# Multi-Sensor-V2_0.net
KiCad netlist of a schematic drawn in Altium Designer
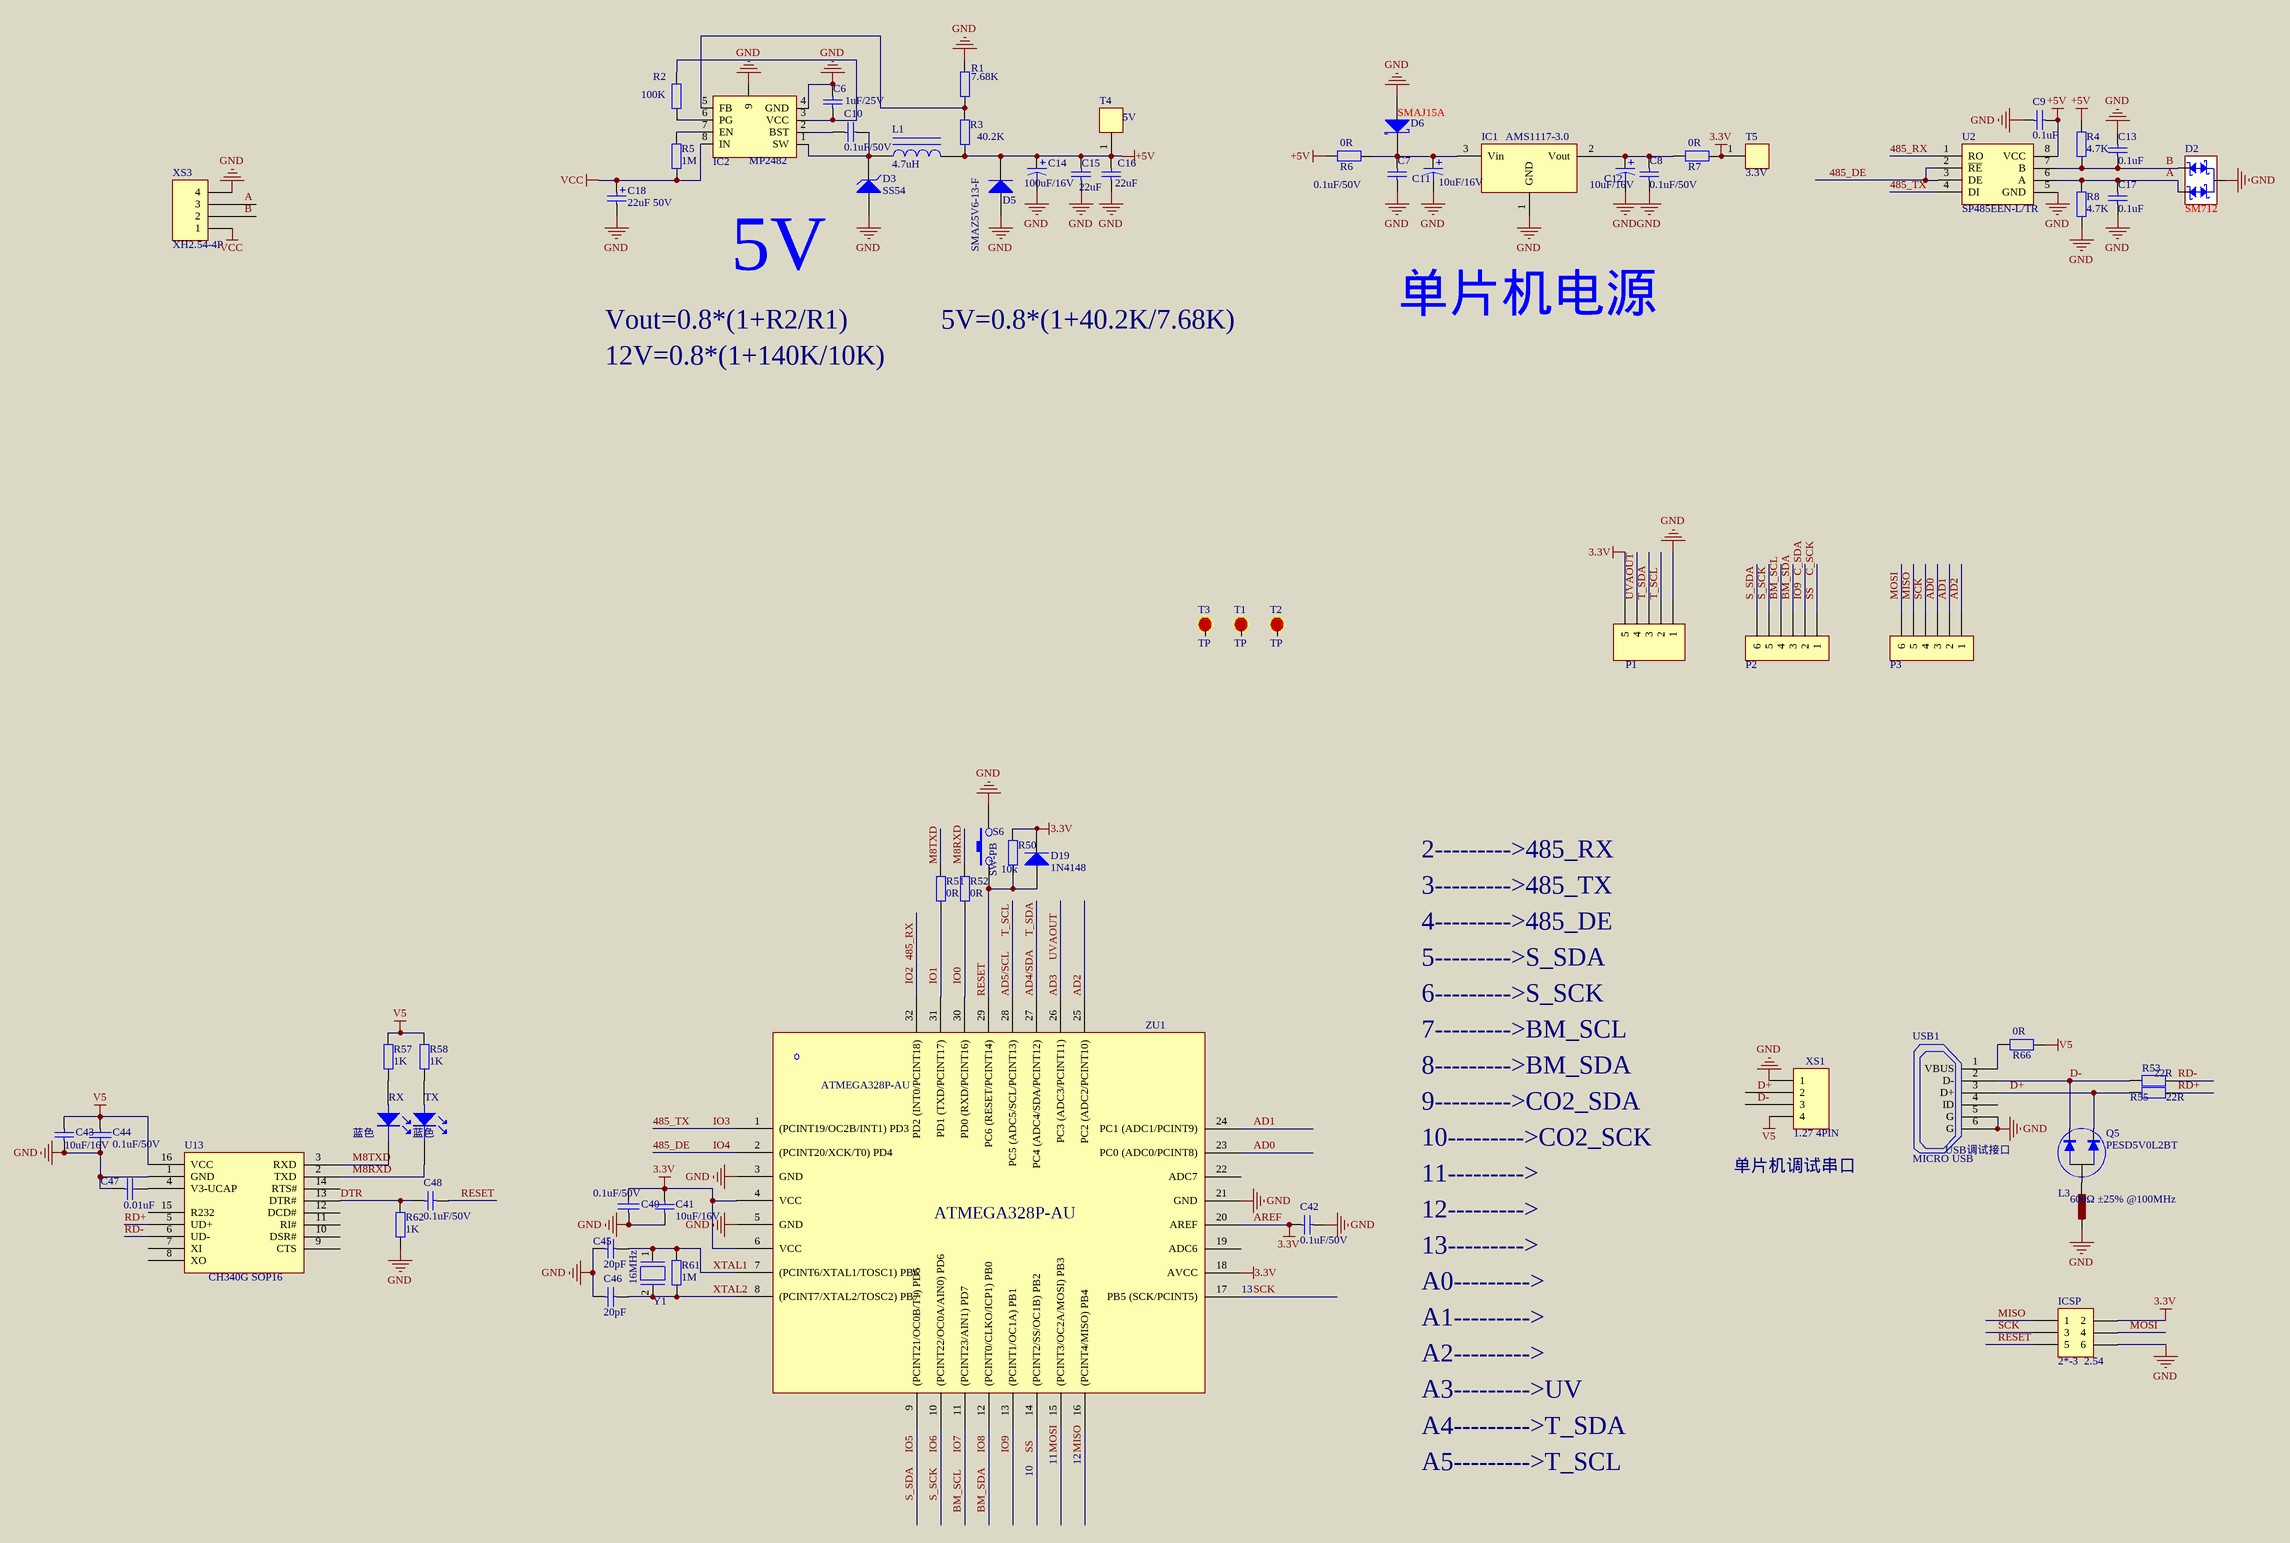
[diagram p0: Multi-Sensor-V2.0.SchDoc]

(export (version "E")
  (design (tool "Eeschema 10.0.6"))
  (components
    (comp (ref "C6")
      (value "1uF/25V")
      (footprint "C-0805")
      (description "贴片电容")
      (fields (field (name "PUBLISHER") "Altium Limited"))
      (libsource (lib "长度计") (part "Cap"))
    )
    (comp (ref "C7")
      (value "0.1uF/50V")
      (footprint "C-0805")
      (description "贴片电容")
      (fields (field (name "PUBLISHER") "Altium Limited"))
      (libsource (lib "Emergency lighting") (part "Cap"))
    )
    (comp (ref "C8")
      (value "0.1uF/50V")
      (footprint "C-0805")
      (description "贴片电容")
      (fields (field (name "PUBLISHER") "Altium Limited"))
      (libsource (lib "Emergency lighting") (part "Cap"))
    )
    (comp (ref "C9")
      (value "0.1uF")
      (footprint "C-0603")
      (description "贴片电容")
      (fields (field (name "PUBLISHER") "Altium Limited"))
      (libsource (lib "Miscellaneous Devices") (part "Cap"))
    )
    (comp (ref "C10")
      (value "0.1uF/50V")
      (footprint "C-0805")
      (description "贴片电容")
      (fields (field (name "PUBLISHER") "Altium Limited"))
      (libsource (lib "Miscellaneous Devices") (part "Cap"))
    )
    (comp (ref "C11")
      (value "10uF/16V")
      (footprint "C-3216")
      (description "钽电容")
      (fields (field (name "PUBLISHER") "Altium Limited"))
      (libsource (lib "kytence") (part "Cap Pol1"))
    )
    (comp (ref "C12")
      (value "10uF/16V")
      (footprint "C-3216")
      (description "钽电容")
      (fields (field (name "PUBLISHER") "Altium Limited"))
      (libsource (lib "kytence") (part "Cap Pol1"))
    )
    (comp (ref "C13")
      (value "0.1uF")
      (footprint "C-0603")
      (description "贴片电容")
      (fields (field (name "PUBLISHER") "Altium Limited"))
      (libsource (lib "Miscellaneous Devices") (part "Cap"))
    )
    (comp (ref "C14")
      (value "100uF/16V")
      (footprint "CAP5*X")
      (description "直插电解电容")
      (fields (field (name "PUBLISHER") "Altium Limited"))
      (libsource (lib "kytence") (part "Cap Pol1"))
    )
    (comp (ref "C15")
      (value "22uF")
      (footprint "C-1206")
      (description "贴片电容")
      (fields (field (name "PUBLISHER") "Altium Limited"))
      (libsource (lib "AirPlaneSign") (part "Cap"))
    )
    (comp (ref "C16")
      (value "22uF")
      (footprint "C-1206")
      (description "贴片电容")
      (fields (field (name "PUBLISHER") "Altium Limited"))
      (libsource (lib "AirPlaneSign") (part "Cap"))
    )
    (comp (ref "C17")
      (value "0.1uF")
      (footprint "C-0603")
      (description "贴片电容")
      (fields (field (name "PUBLISHER") "Altium Limited"))
      (libsource (lib "Miscellaneous Devices") (part "Cap"))
    )
    (comp (ref "C18")
      (value "22uF 50V")
      (footprint "CAP5*X")
      (description "钽电容")
      (libsource (lib "AirPlaneSign") (part "Cap_1"))
    )
    (comp (ref "C40")
      (value "0.1uF/50V")
      (footprint "C-0603")
      (description "贴片电容")
      (libsource (lib "*") (part "CAP"))
    )
    (comp (ref "C41")
      (value "10uF/16V")
      (footprint "C-0805")
      (description "贴片电容")
      (fields (field (name "PUBLISHER") "Altium Limited"))
      (libsource (lib "Miscellaneous Devices") (part "Cap"))
    )
    (comp (ref "C42")
      (value "0.1uF/50V")
      (footprint "C-0603")
      (description "贴片电容")
      (fields (field (name "PUBLISHER") "Altium Limited"))
      (libsource (lib "Miscellaneous Devices") (part "Cap"))
    )
    (comp (ref "C43")
      (value "10uF/16V")
      (footprint "C-0805")
      (description "贴片电容")
      (fields (field (name "PUBLISHER") "Altium Limited"))
      (libsource (lib "Miscellaneous Devices") (part "Cap"))
    )
    (comp (ref "C44")
      (value "0.1uF/50V")
      (footprint "C-0603")
      (description "贴片电容")
      (libsource (lib "*") (part "CAP"))
    )
    (comp (ref "C45")
      (value "20pF")
      (footprint "C-0603")
      (description "贴片电容")
      (fields (field (name "PUBLISHER") "Altium Limited"))
      (libsource (lib "Miscellaneous Devices") (part "Cap"))
    )
    (comp (ref "C46")
      (value "20pF")
      (footprint "C-0603")
      (description "贴片电容")
      (fields (field (name "PUBLISHER") "Altium Limited"))
      (libsource (lib "Miscellaneous Devices") (part "Cap"))
    )
    (comp (ref "C47")
      (value "0.01uF")
      (footprint "C-0603")
      (description "贴片电容")
      (libsource (lib "*") (part "CAP"))
    )
    (comp (ref "C48")
      (value "0.1uF/50V")
      (footprint "C-0603")
      (description "贴片电容")
      (fields (field (name "PUBLISHER") "Altium Limited"))
      (libsource (lib "Miscellaneous Devices") (part "Cap"))
    )
    (comp (ref "D2")
      (value "SM712")
      (footprint "SOT-23-3")
      (description "TVS二极管")
      (fields (field (name "PUBLISHER") "Altium Limited"))
      (libsource (lib "AirPlaneSign") (part "SM712"))
    )
    (comp (ref "D3")
      (value "SS54")
      (footprint "SMA(DO-214AC)")
      (description "肖特基二极管")
      (fields (field (name "PUBLISHER") "Altium Limited"))
      (libsource (lib "Miscellaneous Devices") (part "D Zener"))
    )
    (comp (ref "D5")
      (value "SMAZ5V6-13-F")
      (footprint "SMA(DO-214AC)")
      (description "稳压二极管管")
      (fields (field (name "PUBLISHER") "Altium Limited"))
      (libsource (lib "kytence") (part "Diode"))
    )
    (comp (ref "D6")
      (value "SMAJ15A")
      (footprint "SMA(DO-214AC)")
      (description "TVS二极管")
      (fields (field (name "PUBLISHER") "Altium Limited"))
      (libsource (lib "Emergency lighting") (part "D Schottky"))
    )
    (comp (ref "D19")
      (value "1N4148")
      (footprint "SOD-123")
      (description "开关二极管")
      (libsource (lib "SCHEMATIC") (part "开关二极管"))
    )
    (comp (ref "IC1")
      (value "AMS1117-3.0")
      (footprint "SOT-223")
      (description "电源稳压芯片")
      (libsource (lib "AirPlaneSign") (part "AMS1117-3.0"))
    )
    (comp (ref "IC2")
      (value "MP2482")
      (footprint "SO8 -TP")
      (description "DC-DC芯片")
      (libsource (lib "AirPlaneSign") (part "MP2482"))
    )
    (comp (ref "ICSP")
      (value "2*-3  2.54")
      (footprint "201S2X3")
      (description "单排插针")
      (fields (field (name "PUBLISHER") "Altium Limited"))
      (libsource (lib "AirPlaneSign") (part "Header 2*3"))
    )
    (comp (ref "L1")
      (value "4.7uH")
      (footprint "GDCD8040")
      (description "功率电感")
      (fields (field (name "PUBLISHER") "Altium Limited"))
      (libsource (lib "LLYSCHLib") (part "Inductor Iron"))
    )
    (comp (ref "L3")
      (value "600Ω ±25% @100MHz")
      (footprint "L-0805")
      (description "贴片磁珠")
      (libsource (lib "Miscellaneous Devices") (part "L"))
    )
    (comp (ref "P1")
      (value "JXT-5-l")
      (footprint "JXT-5-l")
      (description "1.27立式贴片针座")
      (fields (field (name "PUBLISHER") "Altium Limited"))
      (libsource (lib "AirPlaneSign") (part "Header 5"))
    )
    (comp (ref "P2")
      (value "JXT-6-l")
      (footprint "JXT-6-l")
      (description "1.27立式贴片针座")
      (fields (field (name "PUBLISHER") "Altium Limited"))
      (libsource (lib "AirPlaneSign") (part "Header 6"))
    )
    (comp (ref "P3")
      (value "JXT-6-l")
      (footprint "JXT-6-l")
      (description "1.27立式贴片针座")
      (fields (field (name "PUBLISHER") "Altium Limited"))
      (libsource (lib "AirPlaneSign") (part "Header 6"))
    )
    (comp (ref "Q5")
      (value "PESD5V0L2BT")
      (footprint "SOT-23-3")
      (description "TVS二极管")
      (libsource (lib "Miscellaneous Devices") (part "ESD1"))
    )
    (comp (ref "R1")
      (value "7.68K")
      (footprint "R-0805")
      (description "贴片电阻")
      (fields (field (name "PUBLISHER") "Altium Limited"))
      (libsource (lib "") (part "Res2_1"))
    )
    (comp (ref "R2")
      (value "100K")
      (footprint "R-0805")
      (description "贴片电阻")
      (fields (field (name "PUBLISHER") "Altium Limited"))
      (libsource (lib "") (part "Res2_1"))
    )
    (comp (ref "R3")
      (value "40.2K")
      (footprint "R-0805")
      (description "贴片电阻")
      (fields (field (name "PUBLISHER") "Altium Limited"))
      (libsource (lib "Miscellaneous Devices") (part "Res2"))
    )
    (comp (ref "R4")
      (value "4.7K")
      (footprint "R-0603")
      (description "贴片电阻")
      (fields (field (name "PUBLISHER") "Altium Limited"))
      (libsource (lib "Miscellaneous Devices") (part "Res2"))
    )
    (comp (ref "R5")
      (value "1M")
      (footprint "R-0805")
      (description "贴片电阻")
      (libsource (lib "SCHEMATIC") (part "贴片电阻"))
    )
    (comp (ref "R6")
      (value "0R")
      (footprint "R-0805")
      (description "贴片电阻")
      (fields (field (name "PUBLISHER") "Altium Limited"))
      (libsource (lib "") (part "Res2_3"))
    )
    (comp (ref "R7")
      (value "0R")
      (footprint "R-0603")
      (description "贴片电阻")
      (fields (field (name "PUBLISHER") "Altium Limited"))
      (libsource (lib "") (part "Res2_3"))
    )
    (comp (ref "R8")
      (value "4.7K")
      (footprint "R-0603")
      (description "贴片电阻")
      (fields (field (name "PUBLISHER") "Altium Limited"))
      (libsource (lib "Miscellaneous Devices") (part "Res2"))
    )
    (comp (ref "R50")
      (value "10k")
      (footprint "R-0603")
      (description "贴片电阻")
      (fields (field (name "PUBLISHER") "Altium Limited"))
      (libsource (lib "Miscellaneous Devices") (part "Res2"))
    )
    (comp (ref "R51")
      (value "0R")
      (footprint "R-0603")
      (description "贴片电阻")
      (fields (field (name "PUBLISHER") "Altium Limited"))
      (libsource (lib "Miscellaneous Devices") (part "Res2"))
    )
    (comp (ref "R52")
      (value "0R")
      (footprint "R-0603")
      (description "贴片电阻")
      (fields (field (name "PUBLISHER") "Altium Limited"))
      (libsource (lib "Miscellaneous Devices") (part "Res2"))
    )
    (comp (ref "R53")
      (value "22R")
      (footprint "R-0603")
      (description "贴片电阻")
      (fields (field (name "PUBLISHER") "Altium Limited"))
      (libsource (lib "") (part "Res2_2"))
    )
    (comp (ref "R55")
      (value "22R")
      (footprint "R-0603")
      (description "贴片电阻")
      (fields (field (name "PUBLISHER") "Altium Limited"))
      (libsource (lib "") (part "Res2_2"))
    )
    (comp (ref "R57")
      (value "1K")
      (footprint "R-0603")
      (description "贴片电阻")
      (fields (field (name "PUBLISHER") "Altium Limited"))
      (libsource (lib "Miscellaneous Devices") (part "Res2"))
    )
    (comp (ref "R58")
      (value "1K")
      (footprint "R-0603")
      (description "贴片电阻")
      (fields (field (name "PUBLISHER") "Altium Limited"))
      (libsource (lib "Miscellaneous Devices") (part "Res2"))
    )
    (comp (ref "R61")
      (value "1M")
      (footprint "R-0603")
      (description "贴片电阻")
      (fields (field (name "PUBLISHER") "Altium Limited"))
      (libsource (lib "Miscellaneous Devices") (part "Res2"))
    )
    (comp (ref "R62")
      (value "1K")
      (footprint "R-0603")
      (description "贴片电阻")
      (fields (field (name "PUBLISHER") "Altium Limited"))
      (libsource (lib "Miscellaneous Devices") (part "Res2"))
    )
    (comp (ref "R66")
      (value "0R")
      (footprint "R-0603")
      (description "贴片电阻")
      (fields (field (name "PUBLISHER") "Altium Limited"))
      (libsource (lib "") (part "Res2_3"))
    )
    (comp (ref "RX")
      (value "蓝色")
      (footprint "LED-0603")
      (description "贴片发光二极管")
      (libsource (lib "Miscellaneous Devices") (part "LED"))
    )
    (comp (ref "S6")
      (value "SW-PB")
      (footprint "轻触(3*6*4.3)")
      (description "微型按键开关")
      (libsource (lib "杂元件库") (part "SW-PB"))
    )
    (comp (ref "T1") (value "TP") (footprint "安装孔-M6") (libsource (lib "AirPlaneSign") (part "TP")))
    (comp (ref "T2") (value "TP") (footprint "安装孔-M6") (libsource (lib "AirPlaneSign") (part "TP")))
    (comp (ref "T3") (value "TP") (footprint "安装孔-M6") (libsource (lib "AirPlaneSign") (part "TP")))
    (comp (ref "T4")
      (value "5V")
      (footprint "TEST_POINT")
      (description "测试点")
      (libsource (lib "InforCenterBoard") (part "TEST_POINT"))
    )
    (comp (ref "T5") (value "3.3V") (footprint "TEST_POINT") (libsource (lib "") (part "TEST_POINT_1")))
    (comp (ref "TX")
      (value "蓝色")
      (footprint "LED-0603")
      (description "贴片发光二极管")
      (libsource (lib "Miscellaneous Devices") (part "LED"))
    )
    (comp (ref "U2")
      (value "SP485EEN-L/TR")
      (footprint "SOP-8_150mil")
      (description "RS485收发芯片")
      (libsource (lib "AirPlaneSign") (part "SP485EEN-L/TR"))
    )
    (comp (ref "U13")
      (value "CH340G SOP16")
      (footprint "SOIC16_39MM")
      (description "USB-TTL接口芯片")
      (libsource (lib "Miscellaneous Devices") (part "CH340G"))
    )
    (comp (ref "USB1")
      (value "MICRO USB")
      (footprint "MICRO_USB")
      (libsource (lib "LEGO") (part "MICRO USB_1"))
    )
    (comp (ref "XS1")
      (value "1.27 4PIN")
      (footprint "JXT-4-l")
      (description "1.27卧式贴片针座")
      (fields (field (name "PUBLISHER") "Altium Limited"))
      (libsource (lib "Miscellaneous Connectors") (part "Header 4"))
    )
    (comp (ref "XS3")
      (value "XH2.54-4P")
      (footprint "XH2.54-4P")
      (description "2.54卧式贴片针座")
      (fields (field (name "PUBLISHER") "Altium Limited"))
      (libsource (lib "") (part "Header 4_1"))
    )
    (comp (ref "Y1")
      (value "16MHz")
      (footprint "hc49s")
      (description "无源晶振")
      (libsource (lib "*") (part "XTAL/S"))
    )
    (comp (ref "ZU1")
      (value "ATMEGA328P-AU")
      (footprint "TQFP-32_7x7x08P")
      (description "单片机")
      (libsource (lib "AirPlaneSign") (part "ATMEGA328P-AU"))
    )
  )
  (nets
    (net (code "1") (name "+5V") (class "Default")
      (node (ref "C14") (pin "1") (pinfunction "1_1") (pintype "passive"))
      (node (ref "C15") (pin "2") (pinfunction "2_2") (pintype "passive"))
      (node (ref "C16") (pin "2") (pinfunction "2_2") (pintype "passive"))
      (node (ref "C9") (pin "2") (pinfunction "2_2") (pintype "passive"))
      (node (ref "D5") (pin "2") (pinfunction "K_2") (pintype "passive"))
      (node (ref "L1") (pin "2") (pinfunction "2_2") (pintype "passive"))
      (node (ref "R3") (pin "2") (pinfunction "2_2") (pintype "passive"))
      (node (ref "R4") (pin "1") (pinfunction "1_1") (pintype "passive"))
      (node (ref "R6") (pin "1") (pinfunction "1_1") (pintype "passive"))
      (node (ref "T4") (pin "1") (pinfunction "1_1") (pintype "passive"))
      (node (ref "U2") (pin "8") (pinfunction "VCC_8") (pintype "power_in"))
    )
    (net (code "2") (name "/485_DE") (class "Default")
      (node (ref "U2") (pin "2") (pinfunction "~{RE}_2") (pintype "power_in"))
      (node (ref "U2") (pin "3") (pinfunction "DE_3") (pintype "power_in"))
      (node (ref "ZU1") (pin "2") (pinfunction "(PCINT20/XCK/T0)_PD4_2") (pintype "passive"))
    )
    (net (code "3") (name "/485_RX") (class "Default")
      (node (ref "U2") (pin "1") (pinfunction "RO_1") (pintype "power_in"))
      (node (ref "ZU1") (pin "32") (pinfunction "PD2_(INT0/PCINT18)_32") (pintype "passive"))
    )
    (net (code "4") (name "/485_TX") (class "Default")
      (node (ref "U2") (pin "4") (pinfunction "DI_4") (pintype "power_in"))
      (node (ref "ZU1") (pin "1") (pinfunction "(PCINT19/OC2B/INT1)_PD3_1") (pintype "passive"))
    )
    (net (code "5") (name "/A") (class "Default")
      (node (ref "C17") (pin "1") (pinfunction "1_1") (pintype "passive"))
      (node (ref "D2") (pin "2") (pinfunction "2_2") (pintype "passive"))
      (node (ref "R8") (pin "1") (pinfunction "1_1") (pintype "passive"))
      (node (ref "U2") (pin "6") (pinfunction "A_6") (pintype "power_in"))
      (node (ref "XS3") (pin "3") (pinfunction "3_3") (pintype "passive"))
    )
    (net (code "6") (name "/AD0") (class "Default")
      (node (ref "P3") (pin "3") (pinfunction "3_3") (pintype "passive"))
      (node (ref "ZU1") (pin "23") (pinfunction "PC0_(ADC0/PCINT8)_23") (pintype "passive"))
    )
    (net (code "7") (name "/AD1") (class "Default")
      (node (ref "P3") (pin "2") (pinfunction "2_2") (pintype "passive"))
      (node (ref "ZU1") (pin "24") (pinfunction "PC1_(ADC1/PCINT9)_24") (pintype "passive"))
    )
    (net (code "8") (name "/AD2") (class "Default")
      (node (ref "P3") (pin "1") (pinfunction "1_1") (pintype "passive"))
      (node (ref "ZU1") (pin "25") (pinfunction "PC2_(ADC2/PCINT10)_25") (pintype "passive"))
    )
    (net (code "9") (name "/AD3") (class "Default")
      (node (ref "P1") (pin "4") (pinfunction "4_4") (pintype "passive"))
      (node (ref "ZU1") (pin "26") (pinfunction "PC3_(ADC3/PCINT11)_26") (pintype "passive"))
    )
    (net (code "10") (name "/AD4{slash}SDA") (class "Default")
      (node (ref "P1") (pin "3") (pinfunction "3_3") (pintype "passive"))
      (node (ref "ZU1") (pin "27") (pinfunction "PC4_(ADC4/SDA/PCINT12)_27") (pintype "passive"))
    )
    (net (code "11") (name "/AD5{slash}SCL") (class "Default")
      (node (ref "P1") (pin "2") (pinfunction "2_2") (pintype "passive"))
      (node (ref "ZU1") (pin "28") (pinfunction "PC5_(ADC5/SCL/PCINT13)_28") (pintype "passive"))
    )
    (net (code "12") (name "/B") (class "Default")
      (node (ref "C13") (pin "2") (pinfunction "2_2") (pintype "passive"))
      (node (ref "D2") (pin "1") (pinfunction "1_1") (pintype "passive"))
      (node (ref "R4") (pin "2") (pinfunction "2_2") (pintype "passive"))
      (node (ref "U2") (pin "7") (pinfunction "B_7") (pintype "power_in"))
      (node (ref "XS3") (pin "2") (pinfunction "2_2") (pintype "passive"))
    )
    (net (code "13") (name "/BM_SCL") (class "Default")
      (node (ref "P2") (pin "4") (pinfunction "4_4") (pintype "passive"))
      (node (ref "ZU1") (pin "11") (pinfunction "(PCINT23/AIN1)_PD7_11") (pintype "passive"))
    )
    (net (code "14") (name "/BM_SDA") (class "Default")
      (node (ref "P2") (pin "3") (pinfunction "3_3") (pintype "passive"))
      (node (ref "ZU1") (pin "12") (pinfunction "(PCINT0/CLKO/ICP1)_PB0_12") (pintype "passive"))
    )
    (net (code "15") (name "/C_SCK") (class "Default")
      (node (ref "P2") (pin "1") (pinfunction "1_1") (pintype "passive"))
      (node (ref "ZU1") (pin "14") (pinfunction "(PCINT2/SS/OC1B)_PB2_14") (pintype "passive"))
    )
    (net (code "16") (name "/C_SDA") (class "Default")
      (node (ref "P2") (pin "2") (pinfunction "2_2") (pintype "passive"))
      (node (ref "ZU1") (pin "13") (pinfunction "(PCINT1/OC1A)_PB1_13") (pintype "passive"))
    )
    (net (code "17") (name "/D+") (class "Default")
      (node (ref "Q5") (pin "2") (pinfunction "2_2") (pintype "passive"))
      (node (ref "R55") (pin "2") (pinfunction "2_2") (pintype "passive"))
      (node (ref "USB1") (pin "3") (pinfunction "D+_3") (pintype "passive"))
      (node (ref "XS1") (pin "2") (pinfunction "2_2") (pintype "passive"))
    )
    (net (code "18") (name "/D-") (class "Default")
      (node (ref "Q5") (pin "1") (pinfunction "1_1") (pintype "passive"))
      (node (ref "R53") (pin "2") (pinfunction "2_2") (pintype "passive"))
      (node (ref "USB1") (pin "2") (pinfunction "D-_2") (pintype "passive"))
      (node (ref "XS1") (pin "3") (pinfunction "3_3") (pintype "passive"))
    )
    (net (code "19") (name "/DTR") (class "Default")
      (node (ref "C48") (pin "2") (pinfunction "2_2") (pintype "passive"))
      (node (ref "R62") (pin "1") (pinfunction "1_1") (pintype "passive"))
      (node (ref "U13") (pin "13") (pinfunction "DTR#_13") (pintype "passive"))
    )
    (net (code "20") (name "/IO0") (class "Default")
      (node (ref "R52") (pin "2") (pinfunction "2_2") (pintype "passive"))
      (node (ref "ZU1") (pin "30") (pinfunction "PD0_(RXD/PCINT16)_30") (pintype "passive"))
    )
    (net (code "21") (name "/IO1") (class "Default")
      (node (ref "R51") (pin "2") (pinfunction "2_2") (pintype "passive"))
      (node (ref "ZU1") (pin "31") (pinfunction "PD1_(TXD/PCINT17)_31") (pintype "passive"))
    )
    (net (code "22") (name "/IO5") (class "Default")
      (node (ref "P2") (pin "6") (pinfunction "6_6") (pintype "passive"))
      (node (ref "ZU1") (pin "9") (pinfunction "(PCINT21/OC0B/T1)_PD5_9") (pintype "passive"))
    )
    (net (code "23") (name "/IO6") (class "Default")
      (node (ref "P2") (pin "5") (pinfunction "5_5") (pintype "passive"))
      (node (ref "ZU1") (pin "10") (pinfunction "(PCINT22/OC0A/AIN0)_PD6_10") (pintype "passive"))
    )
    (net (code "24") (name "/M8RXD") (class "Default")
      (node (ref "R52") (pin "1") (pinfunction "1_1") (pintype "passive"))
      (node (ref "TX") (pin "K") (pinfunction "2_K") (pintype "passive"))
      (node (ref "U13") (pin "2") (pinfunction "TXD_2") (pintype "passive"))
    )
    (net (code "25") (name "/M8TXD") (class "Default")
      (node (ref "R51") (pin "1") (pinfunction "1_1") (pintype "passive"))
      (node (ref "RX") (pin "K") (pinfunction "2_K") (pintype "passive"))
      (node (ref "U13") (pin "3") (pinfunction "RXD_3") (pintype "passive"))
    )
    (net (code "26") (name "/MISO") (class "Default")
      (node (ref "ICSP") (pin "1") (pinfunction "1_1") (pintype "passive"))
      (node (ref "P3") (pin "5") (pinfunction "5_5") (pintype "passive"))
      (node (ref "ZU1") (pin "16") (pinfunction "(PCINT4/MISO)_PB4_16") (pintype "passive"))
    )
    (net (code "27") (name "/MOSI") (class "Default")
      (node (ref "ICSP") (pin "4") (pinfunction "4_4") (pintype "passive"))
      (node (ref "P3") (pin "6") (pinfunction "6_6") (pintype "passive"))
      (node (ref "ZU1") (pin "15") (pinfunction "(PCINT3/OC2A/MOSI)_PB3_15") (pintype "passive"))
    )
    (net (code "28") (name "/RD+") (class "Default")
      (node (ref "R55") (pin "1") (pinfunction "1_1") (pintype "passive"))
      (node (ref "U13") (pin "5") (pinfunction "UD+_5") (pintype "passive"))
    )
    (net (code "29") (name "/RD-") (class "Default")
      (node (ref "R53") (pin "1") (pinfunction "1_1") (pintype "passive"))
      (node (ref "U13") (pin "6") (pinfunction "UD-_6") (pintype "passive"))
    )
    (net (code "30") (name "/RESET") (class "Default")
      (node (ref "C48") (pin "1") (pinfunction "1_1") (pintype "passive"))
      (node (ref "D19") (pin "1") (pinfunction "A_1") (pintype "passive"))
      (node (ref "ICSP") (pin "5") (pinfunction "5_5") (pintype "passive"))
      (node (ref "R50") (pin "2") (pinfunction "2_2") (pintype "passive"))
      (node (ref "S6") (pin "1") (pinfunction "1_1") (pintype "passive"))
      (node (ref "ZU1") (pin "29") (pinfunction "PC6_(RESET/PCINT14)_29") (pintype "passive"))
    )
    (net (code "31") (name "/SCK") (class "Default")
      (node (ref "ICSP") (pin "3") (pinfunction "3_3") (pintype "passive"))
      (node (ref "P3") (pin "4") (pinfunction "4_4") (pintype "passive"))
      (node (ref "ZU1") (pin "17") (pinfunction "PB5_(SCK/PCINT5)_17") (pintype "passive"))
    )
    (net (code "32") (name "/XTAL1") (class "Default")
      (node (ref "C45") (pin "2") (pinfunction "2_2") (pintype "passive"))
      (node (ref "R61") (pin "1") (pinfunction "1_1") (pintype "passive"))
      (node (ref "Y1") (pin "1") (pinfunction "1_1") (pintype "passive"))
      (node (ref "ZU1") (pin "7") (pinfunction "(PCINT6/XTAL1/TOSC1)_PB6_7") (pintype "passive"))
    )
    (net (code "33") (name "/XTAL2") (class "Default")
      (node (ref "C46") (pin "2") (pinfunction "2_2") (pintype "passive"))
      (node (ref "R61") (pin "2") (pinfunction "2_2") (pintype "passive"))
      (node (ref "Y1") (pin "2") (pinfunction "2_2") (pintype "passive"))
      (node (ref "ZU1") (pin "8") (pinfunction "(PCINT7/XTAL2/TOSC2)_PB7_8") (pintype "passive"))
    )
    (net (code "34") (name "3.3V") (class "Default")
      (node (ref "C40") (pin "2") (pinfunction "2_2") (pintype "passive"))
      (node (ref "C41") (pin "2") (pinfunction "2_2") (pintype "passive"))
      (node (ref "C42") (pin "2") (pinfunction "2_2") (pintype "passive"))
      (node (ref "D19") (pin "2") (pinfunction "K_2") (pintype "passive"))
      (node (ref "ICSP") (pin "2") (pinfunction "2_2") (pintype "passive"))
      (node (ref "P1") (pin "5") (pinfunction "5_5") (pintype "passive"))
      (node (ref "R50") (pin "1") (pinfunction "1_1") (pintype "passive"))
      (node (ref "R7") (pin "2") (pinfunction "2_2") (pintype "passive"))
      (node (ref "T5") (pin "1") (pinfunction "1_1") (pintype "passive"))
      (node (ref "ZU1") (pin "18") (pinfunction "AVCC_18") (pintype "passive"))
      (node (ref "ZU1") (pin "20") (pinfunction "AREF_20") (pintype "passive"))
      (node (ref "ZU1") (pin "4") (pinfunction "VCC_4") (pintype "passive"))
      (node (ref "ZU1") (pin "6") (pinfunction "VCC_6") (pintype "passive"))
    )
    (net (code "35") (name "GND") (class "Default")
      (node (ref "C11") (pin "2") (pinfunction "2_2") (pintype "passive"))
      (node (ref "C12") (pin "2") (pinfunction "2_2") (pintype "passive"))
      (node (ref "C13") (pin "1") (pinfunction "1_1") (pintype "passive"))
      (node (ref "C14") (pin "2") (pinfunction "2_2") (pintype "passive"))
      (node (ref "C15") (pin "1") (pinfunction "1_1") (pintype "passive"))
      (node (ref "C16") (pin "1") (pinfunction "1_1") (pintype "passive"))
      (node (ref "C17") (pin "2") (pinfunction "2_2") (pintype "passive"))
      (node (ref "C18") (pin "2") (pinfunction "2_2") (pintype "passive"))
      (node (ref "C40") (pin "1") (pinfunction "1_1") (pintype "passive"))
      (node (ref "C41") (pin "1") (pinfunction "1_1") (pintype "passive"))
      (node (ref "C42") (pin "1") (pinfunction "1_1") (pintype "passive"))
      (node (ref "C43") (pin "2") (pinfunction "2_2") (pintype "passive"))
      (node (ref "C44") (pin "2") (pinfunction "2_2") (pintype "passive"))
      (node (ref "C45") (pin "1") (pinfunction "1_1") (pintype "passive"))
      (node (ref "C46") (pin "1") (pinfunction "1_1") (pintype "passive"))
      (node (ref "C47") (pin "1") (pinfunction "1_1") (pintype "passive"))
      (node (ref "C6") (pin "1") (pinfunction "1_1") (pintype "passive"))
      (node (ref "C7") (pin "1") (pinfunction "1_1") (pintype "passive"))
      (node (ref "C8") (pin "1") (pinfunction "1_1") (pintype "passive"))
      (node (ref "C9") (pin "1") (pinfunction "1_1") (pintype "passive"))
      (node (ref "D2") (pin "3") (pinfunction "3_3") (pintype "passive"))
      (node (ref "D3") (pin "1") (pinfunction "A_1") (pintype "passive"))
      (node (ref "D5") (pin "1") (pinfunction "A_1") (pintype "passive"))
      (node (ref "D6") (pin "1") (pinfunction "A_1") (pintype "passive"))
      (node (ref "IC1") (pin "1") (pinfunction "GND_1") (pintype "passive"))
      (node (ref "IC2") (pin "4") (pinfunction "GND_4") (pintype "passive"))
      (node (ref "IC2") (pin "9") (pinfunction "9_9") (pintype "passive"))
      (node (ref "ICSP") (pin "6") (pinfunction "6_6") (pintype "passive"))
      (node (ref "L3") (pin "2") (pintype "passive"))
      (node (ref "P1") (pin "1") (pinfunction "1_1") (pintype "passive"))
      (node (ref "R1") (pin "2") (pinfunction "2_2") (pintype "passive"))
      (node (ref "R62") (pin "2") (pinfunction "2_2") (pintype "passive"))
      (node (ref "R8") (pin "2") (pinfunction "2_2") (pintype "passive"))
      (node (ref "S6") (pin "2") (pinfunction "2_2") (pintype "passive"))
      (node (ref "U13") (pin "1") (pinfunction "GND_1") (pintype "passive"))
      (node (ref "U2") (pin "5") (pinfunction "GND_5") (pintype "power_in"))
      (node (ref "USB1") (pin "5") (pinfunction "G_5") (pintype "passive"))
      (node (ref "USB1") (pin "6") (pinfunction "G_6") (pintype "passive"))
      (node (ref "XS1") (pin "1") (pinfunction "1_1") (pintype "passive"))
      (node (ref "XS3") (pin "4") (pinfunction "4_4") (pintype "passive"))
      (node (ref "ZU1") (pin "21") (pinfunction "GND_21") (pintype "passive"))
      (node (ref "ZU1") (pin "3") (pinfunction "GND_3") (pintype "passive"))
      (node (ref "ZU1") (pin "5") (pinfunction "GND_5") (pintype "passive"))
    )
    (net (code "36") (name "Net-(D3-K)") (class "Default")
      (node (ref "C10") (pin "1") (pinfunction "1_1") (pintype "passive"))
      (node (ref "D3") (pin "2") (pinfunction "K_2") (pintype "passive"))
      (node (ref "IC2") (pin "1") (pinfunction "SW_1") (pintype "passive"))
      (node (ref "L1") (pin "1") (pinfunction "1_1") (pintype "passive"))
    )
    (net (code "37") (name "Net-(D6-K)") (class "Default")
      (node (ref "C11") (pin "1") (pinfunction "1_1") (pintype "passive"))
      (node (ref "C7") (pin "2") (pinfunction "2_2") (pintype "passive"))
      (node (ref "D6") (pin "2") (pinfunction "K_2") (pintype "passive"))
      (node (ref "IC1") (pin "3") (pinfunction "Vin_3") (pintype "passive"))
      (node (ref "R6") (pin "2") (pinfunction "2_2") (pintype "passive"))
    )
    (net (code "38") (name "Net-(IC1-Vout)") (class "Default")
      (node (ref "C12") (pin "1") (pinfunction "1_1") (pintype "passive"))
      (node (ref "C8") (pin "2") (pinfunction "2_2") (pintype "passive"))
      (node (ref "IC1") (pin "2") (pinfunction "Vout_2") (pintype "passive"))
      (node (ref "R7") (pin "1") (pinfunction "1_1") (pintype "passive"))
    )
    (net (code "39") (name "Net-(IC2-BST)") (class "Default")
      (node (ref "C10") (pin "2") (pinfunction "2_2") (pintype "passive"))
      (node (ref "IC2") (pin "2") (pinfunction "BST_2") (pintype "passive"))
    )
    (net (code "40") (name "Net-(IC2-EN)") (class "Default")
      (node (ref "IC2") (pin "7") (pinfunction "EN_7") (pintype "passive"))
      (node (ref "R5") (pin "2") (pinfunction "2_2") (pintype "passive"))
    )
    (net (code "41") (name "Net-(IC2-FB)") (class "Default")
      (node (ref "IC2") (pin "5") (pinfunction "FB_5") (pintype "passive"))
      (node (ref "R1") (pin "1") (pinfunction "1_1") (pintype "passive"))
      (node (ref "R3") (pin "1") (pinfunction "1_1") (pintype "passive"))
    )
    (net (code "42") (name "Net-(IC2-PG)") (class "Default")
      (node (ref "IC2") (pin "6") (pinfunction "PG_6") (pintype "passive"))
      (node (ref "R2") (pin "1") (pinfunction "1_1") (pintype "passive"))
    )
    (net (code "43") (name "Net-(IC2-VCC)") (class "Default")
      (node (ref "C6") (pin "2") (pinfunction "2_2") (pintype "passive"))
      (node (ref "IC2") (pin "3") (pinfunction "VCC_3") (pintype "passive"))
      (node (ref "R2") (pin "2") (pinfunction "2_2") (pintype "passive"))
    )
    (net (code "44") (name "Net-(L3-Pad1)") (class "Default")
      (node (ref "L3") (pin "1") (pintype "passive"))
      (node (ref "Q5") (pin "3") (pinfunction "3_3") (pintype "passive"))
    )
    (net (code "45") (name "Net-(RX-1)") (class "Default")
      (node (ref "R57") (pin "2") (pinfunction "2_2") (pintype "passive"))
      (node (ref "RX") (pin "A") (pinfunction "1_A") (pintype "passive"))
    )
    (net (code "46") (name "Net-(TX-1)") (class "Default")
      (node (ref "R58") (pin "2") (pinfunction "2_2") (pintype "passive"))
      (node (ref "TX") (pin "A") (pinfunction "1_A") (pintype "passive"))
    )
    (net (code "47") (name "Net-(U13-V3-UCAP)") (class "Default")
      (node (ref "C47") (pin "2") (pinfunction "2_2") (pintype "passive"))
      (node (ref "U13") (pin "4") (pinfunction "V3-UCAP_4") (pintype "passive"))
    )
    (net (code "48") (name "Net-(USB1-VBUS)") (class "Default")
      (node (ref "R66") (pin "1") (pinfunction "1_1") (pintype "passive"))
      (node (ref "USB1") (pin "1") (pinfunction "VBUS_1") (pintype "passive"))
    )
    (net (code "49") (name "V5") (class "Default")
      (node (ref "C43") (pin "1") (pinfunction "1_1") (pintype "passive"))
      (node (ref "C44") (pin "1") (pinfunction "1_1") (pintype "passive"))
      (node (ref "R57") (pin "1") (pinfunction "1_1") (pintype "passive"))
      (node (ref "R58") (pin "1") (pinfunction "1_1") (pintype "passive"))
      (node (ref "R66") (pin "2") (pinfunction "2_2") (pintype "passive"))
      (node (ref "U13") (pin "16") (pinfunction "VCC_16") (pintype "passive"))
      (node (ref "XS1") (pin "4") (pinfunction "4_4") (pintype "passive"))
    )
    (net (code "50") (name "VCC") (class "Default")
      (node (ref "C18") (pin "1") (pinfunction "1_1") (pintype "passive"))
      (node (ref "IC2") (pin "8") (pinfunction "IN_8") (pintype "passive"))
      (node (ref "R5") (pin "1") (pinfunction "1_1") (pintype "passive"))
      (node (ref "XS3") (pin "1") (pinfunction "1_1") (pintype "passive"))
    )
    (net (code "51") (name "unconnected-(T1-T-Pad1)") (class "Default")
      (node (ref "T1") (pin "1") (pinfunction "T_1") (pintype "passive"))
    )
    (net (code "52") (name "unconnected-(T2-T-Pad1)") (class "Default")
      (node (ref "T2") (pin "1") (pinfunction "T_1") (pintype "passive"))
    )
    (net (code "53") (name "unconnected-(T3-T-Pad1)") (class "Default")
      (node (ref "T3") (pin "1") (pinfunction "T_1") (pintype "passive"))
    )
    (net (code "54") (name "unconnected-(U13-CTS-Pad9)") (class "Default")
      (node (ref "U13") (pin "9") (pinfunction "CTS_9") (pintype "passive"))
    )
    (net (code "55") (name "unconnected-(U13-DCD#-Pad12)") (class "Default")
      (node (ref "U13") (pin "12") (pinfunction "DCD#_12") (pintype "passive"))
    )
    (net (code "56") (name "unconnected-(U13-DSR#-Pad10)") (class "Default")
      (node (ref "U13") (pin "10") (pinfunction "DSR#_10") (pintype "passive"))
    )
    (net (code "57") (name "unconnected-(U13-R232-Pad15)") (class "Default")
      (node (ref "U13") (pin "15") (pinfunction "R232_15") (pintype "passive"))
    )
    (net (code "58") (name "unconnected-(U13-RI#-Pad11)") (class "Default")
      (node (ref "U13") (pin "11") (pinfunction "RI#_11") (pintype "passive"))
    )
    (net (code "59") (name "unconnected-(U13-RTS#-Pad14)") (class "Default")
      (node (ref "U13") (pin "14") (pinfunction "RTS#_14") (pintype "passive"))
    )
    (net (code "60") (name "unconnected-(U13-XI-Pad7)") (class "Default")
      (node (ref "U13") (pin "7") (pinfunction "XI_7") (pintype "passive"))
    )
    (net (code "61") (name "unconnected-(U13-XO-Pad8)") (class "Default")
      (node (ref "U13") (pin "8") (pinfunction "XO_8") (pintype "passive"))
    )
    (net (code "62") (name "unconnected-(USB1-ID-Pad4)") (class "Default")
      (node (ref "USB1") (pin "4") (pinfunction "ID_4") (pintype "passive"))
    )
    (net (code "63") (name "unconnected-(ZU1-ADC6-Pad19)") (class "Default")
      (node (ref "ZU1") (pin "19") (pinfunction "ADC6_19") (pintype "passive"))
    )
    (net (code "64") (name "unconnected-(ZU1-ADC7-Pad22)") (class "Default")
      (node (ref "ZU1") (pin "22") (pinfunction "ADC7_22") (pintype "passive"))
    )
  )
)
